# Connector.net
KiCad netlist of a schematic drawn in Altium Designer
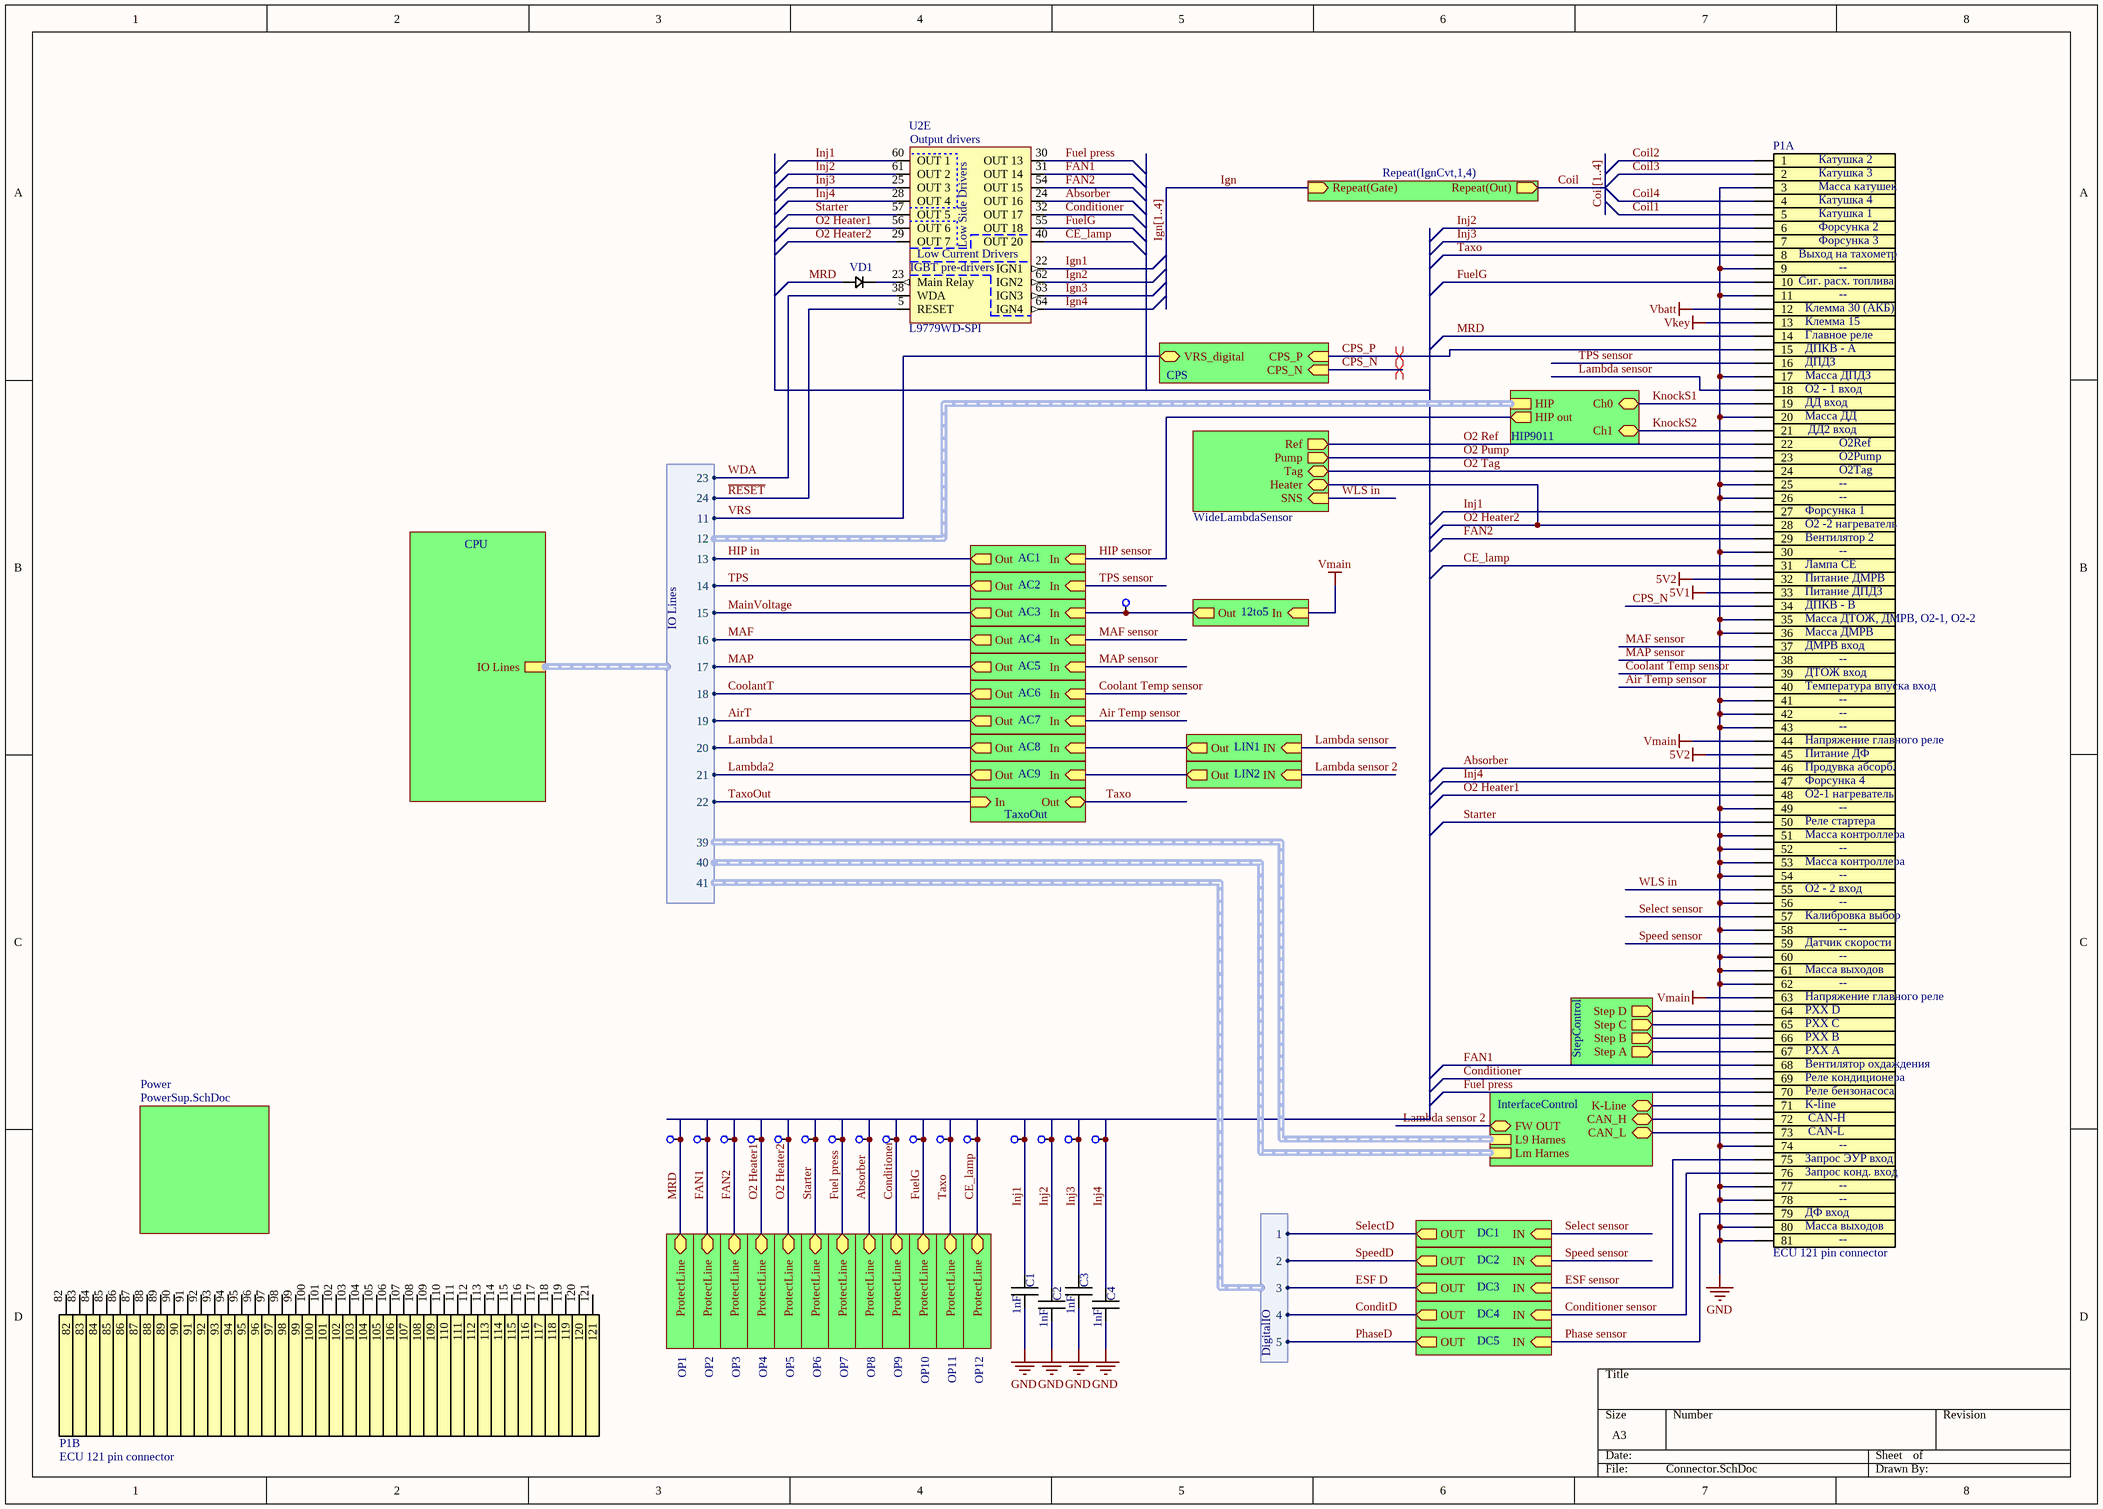
[diagram p0: Connector.SchDoc]

(export (version "E")
  (design (tool "Eeschema 10.0.6"))
  (components
    (comp (ref "C1")
      (value "1nF")
      (footprint "SMD 0603")
      (description "CC0603KRX7R9BB102")
      (libsource (lib "Maks_lib") (part "Capasitor"))
    )
    (comp (ref "C2")
      (value "1nF")
      (footprint "SMD 0603")
      (description "CC0603KRX7R9BB102")
      (libsource (lib "Maks_lib") (part "Capasitor"))
    )
    (comp (ref "C3")
      (value "1nF")
      (footprint "SMD 0603")
      (description "CC0603KRX7R9BB102")
      (libsource (lib "Maks_lib") (part "Capasitor"))
    )
    (comp (ref "C4")
      (value "1nF")
      (footprint "SMD 0603")
      (description "CC0603KRX7R9BB102")
      (libsource (lib "Maks_lib") (part "Capasitor"))
    )
    (comp (ref "P1")
      (value "ECU 121 pin connector")
      (footprint "1241434-1")
      (libsource (lib "Maks_lib") (part "1241434-1"))
    )
    (comp (ref "TP1")
      (value "TestPoint")
      (footprint "TESTPOINT")
      (description "testPoint")
      (libsource (lib "Maks_lib") (part "TestPoint"))
    )
    (comp (ref "TP2")
      (value "TestPoint")
      (footprint "TESTPOINT")
      (description "testPoint")
      (libsource (lib "Maks_lib") (part "TestPoint"))
    )
    (comp (ref "TP3")
      (value "TestPoint")
      (footprint "TESTPOINT")
      (description "testPoint")
      (libsource (lib "Maks_lib") (part "TestPoint"))
    )
    (comp (ref "TP4")
      (value "TestPoint")
      (footprint "TESTPOINT")
      (description "testPoint")
      (libsource (lib "Maks_lib") (part "TestPoint"))
    )
    (comp (ref "TP5")
      (value "TestPoint")
      (footprint "TESTPOINT")
      (description "testPoint")
      (libsource (lib "Maks_lib") (part "TestPoint"))
    )
    (comp (ref "TP6")
      (value "TestPoint")
      (footprint "TESTPOINT")
      (description "testPoint")
      (libsource (lib "Maks_lib") (part "TestPoint"))
    )
    (comp (ref "TP7")
      (value "TestPoint")
      (footprint "TESTPOINT")
      (description "testPoint")
      (libsource (lib "Maks_lib") (part "TestPoint"))
    )
    (comp (ref "TP8")
      (value "TestPoint")
      (footprint "TESTPOINT")
      (description "testPoint")
      (libsource (lib "Maks_lib") (part "TestPoint"))
    )
    (comp (ref "TP9")
      (value "TestPoint")
      (footprint "TESTPOINT")
      (description "testPoint")
      (libsource (lib "Maks_lib") (part "TestPoint"))
    )
    (comp (ref "TP10")
      (value "TestPoint")
      (footprint "TESTPOINT")
      (description "testPoint")
      (libsource (lib "Maks_lib") (part "TestPoint"))
    )
    (comp (ref "TP11")
      (value "TestPoint")
      (footprint "TESTPOINT")
      (description "testPoint")
      (libsource (lib "Maks_lib") (part "TestPoint"))
    )
    (comp (ref "TP12")
      (value "TestPoint")
      (footprint "TESTPOINT")
      (description "testPoint")
      (libsource (lib "Maks_lib") (part "TestPoint"))
    )
    (comp (ref "TP13")
      (value "TestPoint")
      (footprint "TESTPOINT")
      (description "testPoint")
      (libsource (lib "Maks_lib") (part "TestPoint"))
    )
    (comp (ref "TP14")
      (value "TestPoint")
      (footprint "TESTPOINT")
      (description "testPoint")
      (libsource (lib "Maks_lib") (part "TestPoint"))
    )
    (comp (ref "TP15")
      (value "TestPoint")
      (footprint "TESTPOINT")
      (description "testPoint")
      (libsource (lib "Maks_lib") (part "TestPoint"))
    )
    (comp (ref "TP16")
      (value "TestPoint")
      (footprint "TESTPOINT")
      (description "testPoint")
      (libsource (lib "Maks_lib") (part "TestPoint"))
    )
    (comp (ref "TP17")
      (value "TestPoint")
      (footprint "TESTPOINT")
      (description "testPoint")
      (libsource (lib "Maks_lib") (part "TestPoint"))
    )
    (comp (ref "U2")
      (value "L9779WD-SPI")
      (footprint "HiQUAD-64")
      (description "Multifunction IC for engine management system")
      (libsource (lib "Maks_lib") (part "L9779WD-SPI"))
    )
    (comp (ref "VD1")
      (value "Diode")
      (footprint "DO-214AC")
      (description "STTH2R02A")
      (libsource (lib "Maks_lib") (part "Diode"))
    )
  )
  (nets
    (net (code "3") (name "/Absorber") (class "Default")
      (node (ref "P1") (pin "46") (pinfunction "46_46") (pintype "passive"))
      (node (ref "TP8") (pin "0") (pinfunction "0_0") (pintype "passive"))
      (node (ref "U2") (pin "24") (pinfunction "OUT_16_24") (pintype "passive"))
    )
    (net (code "4") (name "/Air Temp sensor") (class "Default")
      (node (ref "P1") (pin "40") (pinfunction "40_40") (pintype "passive"))
    )
    (net (code "6") (name "/CAN_H") (class "Default")
      (node (ref "P1") (pin "72") (pinfunction "72_72") (pintype "passive"))
    )
    (net (code "7") (name "/CAN_L") (class "Default")
      (node (ref "P1") (pin "73") (pinfunction "73_73") (pintype "passive"))
    )
    (net (code "8") (name "/CE_lamp") (class "Default")
      (node (ref "P1") (pin "31") (pinfunction "31_31") (pintype "passive"))
      (node (ref "TP12") (pin "0") (pinfunction "0_0") (pintype "passive"))
      (node (ref "U2") (pin "40") (pinfunction "OUT_20_40") (pintype "passive"))
    )
    (net (code "9") (name "/CPS_N") (class "Default")
      (node (ref "P1") (pin "34") (pinfunction "34_34") (pintype "passive"))
    )
    (net (code "10") (name "/CPS_P") (class "Default")
      (node (ref "P1") (pin "15") (pinfunction "15_15") (pintype "passive"))
    )
    (net (code "12") (name "/Coil1") (class "Default")
      (node (ref "P1") (pin "5") (pinfunction "5_5") (pintype "passive"))
    )
    (net (code "13") (name "/Coil2") (class "Default")
      (node (ref "P1") (pin "1") (pinfunction "1_1") (pintype "passive"))
    )
    (net (code "14") (name "/Coil3") (class "Default")
      (node (ref "P1") (pin "2") (pinfunction "2_2") (pintype "passive"))
    )
    (net (code "15") (name "/Coil4") (class "Default")
      (node (ref "P1") (pin "4") (pinfunction "4_4") (pintype "passive"))
    )
    (net (code "18") (name "/Conditioner") (class "Default")
      (node (ref "P1") (pin "69") (pinfunction "69_69") (pintype "passive"))
      (node (ref "TP9") (pin "0") (pinfunction "0_0") (pintype "passive"))
      (node (ref "U2") (pin "32") (pinfunction "OUT_17_32") (pintype "passive"))
    )
    (net (code "19") (name "/Conditioner sensor") (class "Default")
      (node (ref "P1") (pin "76") (pinfunction "76_76") (pintype "passive"))
    )
    (net (code "20") (name "/Coolant Temp sensor") (class "Default")
      (node (ref "P1") (pin "39") (pinfunction "39_39") (pintype "passive"))
    )
    (net (code "23") (name "/ESF sensor") (class "Default")
      (node (ref "P1") (pin "75") (pinfunction "75_75") (pintype "passive"))
    )
    (net (code "24") (name "/FAN1") (class "Default")
      (node (ref "P1") (pin "68") (pinfunction "68_68") (pintype "passive"))
      (node (ref "TP2") (pin "0") (pinfunction "0_0") (pintype "passive"))
      (node (ref "U2") (pin "31") (pinfunction "OUT_14_31") (pintype "passive"))
    )
    (net (code "25") (name "/FAN2") (class "Default")
      (node (ref "P1") (pin "29") (pinfunction "29_29") (pintype "passive"))
      (node (ref "TP3") (pin "0") (pinfunction "0_0") (pintype "passive"))
      (node (ref "U2") (pin "54") (pinfunction "OUT_15_54") (pintype "passive"))
    )
    (net (code "26") (name "/Fuel press") (class "Default")
      (node (ref "P1") (pin "70") (pinfunction "70_70") (pintype "passive"))
      (node (ref "TP7") (pin "0") (pinfunction "0_0") (pintype "passive"))
      (node (ref "U2") (pin "30") (pinfunction "OUT_13_30") (pintype "passive"))
    )
    (net (code "27") (name "/FuelG") (class "Default")
      (node (ref "P1") (pin "10") (pinfunction "10_10") (pintype "passive"))
      (node (ref "TP10") (pin "0") (pinfunction "0_0") (pintype "passive"))
      (node (ref "U2") (pin "55") (pinfunction "OUT_18_55") (pintype "passive"))
    )
    (net (code "33") (name "/Ign1") (class "Default")
      (node (ref "U2") (pin "22") (pinfunction "IGN1_22") (pintype "output"))
    )
    (net (code "34") (name "/Ign2") (class "Default")
      (node (ref "U2") (pin "62") (pinfunction "IGN2_62") (pintype "output"))
    )
    (net (code "35") (name "/Ign3") (class "Default")
      (node (ref "U2") (pin "63") (pinfunction "IGN3_63") (pintype "output"))
    )
    (net (code "36") (name "/Ign4") (class "Default")
      (node (ref "U2") (pin "64") (pinfunction "IGN4_64") (pintype "output"))
    )
    (net (code "38") (name "/Inj1") (class "Default")
      (node (ref "C1") (pin "2") (pinfunction "2_2") (pintype "passive"))
      (node (ref "P1") (pin "27") (pinfunction "27_27") (pintype "passive"))
      (node (ref "TP13") (pin "0") (pinfunction "0_0") (pintype "passive"))
      (node (ref "U2") (pin "60") (pinfunction "OUT_1_60") (pintype "passive"))
    )
    (net (code "39") (name "/Inj2") (class "Default")
      (node (ref "C2") (pin "2") (pinfunction "2_2") (pintype "passive"))
      (node (ref "P1") (pin "6") (pinfunction "6_6") (pintype "passive"))
      (node (ref "TP14") (pin "0") (pinfunction "0_0") (pintype "passive"))
      (node (ref "U2") (pin "61") (pinfunction "OUT_2_61") (pintype "passive"))
    )
    (net (code "40") (name "/Inj3") (class "Default")
      (node (ref "C3") (pin "2") (pinfunction "2_2") (pintype "passive"))
      (node (ref "P1") (pin "7") (pinfunction "7_7") (pintype "passive"))
      (node (ref "TP15") (pin "0") (pinfunction "0_0") (pintype "passive"))
      (node (ref "U2") (pin "25") (pinfunction "OUT_3_25") (pintype "passive"))
    )
    (net (code "41") (name "/Inj4") (class "Default")
      (node (ref "C4") (pin "2") (pinfunction "2_2") (pintype "passive"))
      (node (ref "P1") (pin "47") (pinfunction "47_47") (pintype "passive"))
      (node (ref "TP16") (pin "0") (pinfunction "0_0") (pintype "passive"))
      (node (ref "U2") (pin "28") (pinfunction "OUT_4_28") (pintype "passive"))
    )
    (net (code "42") (name "/K-Line") (class "Default")
      (node (ref "P1") (pin "71") (pinfunction "71_71") (pintype "passive"))
    )
    (net (code "43") (name "/KnockS1") (class "Default")
      (node (ref "P1") (pin "19") (pinfunction "19_19") (pintype "passive"))
    )
    (net (code "44") (name "/KnockS2") (class "Default")
      (node (ref "P1") (pin "21") (pinfunction "21_21") (pintype "passive"))
    )
    (net (code "46") (name "/Lambda sensor") (class "Default")
      (node (ref "P1") (pin "18") (pinfunction "18_18") (pintype "passive"))
    )
    (net (code "52") (name "/MAF sensor") (class "Default")
      (node (ref "P1") (pin "37") (pinfunction "37_37") (pintype "passive"))
    )
    (net (code "54") (name "/MAP sensor") (class "Default")
      (node (ref "P1") (pin "38") (pinfunction "38_38") (pintype "passive"))
    )
    (net (code "55") (name "/MRD") (class "Default")
      (node (ref "P1") (pin "14") (pinfunction "14_14") (pintype "passive"))
      (node (ref "TP1") (pin "0") (pinfunction "0_0") (pintype "passive"))
      (node (ref "VD1") (pin "0") (pinfunction "0_0") (pintype "passive"))
    )
    (net (code "57") (name "/O2 Heater1") (class "Default")
      (node (ref "P1") (pin "48") (pinfunction "48_48") (pintype "passive"))
      (node (ref "TP4") (pin "0") (pinfunction "0_0") (pintype "passive"))
      (node (ref "U2") (pin "56") (pinfunction "OUT_6_56") (pintype "passive"))
    )
    (net (code "58") (name "/O2 Heater2") (class "Default")
      (node (ref "P1") (pin "28") (pinfunction "28_28") (pintype "passive"))
      (node (ref "TP5") (pin "0") (pinfunction "0_0") (pintype "passive"))
      (node (ref "U2") (pin "29") (pinfunction "OUT_7_29") (pintype "passive"))
    )
    (net (code "59") (name "/O2 Pump") (class "Default")
      (node (ref "P1") (pin "23") (pinfunction "23_23") (pintype "passive"))
    )
    (net (code "60") (name "/O2 Ref") (class "Default")
      (node (ref "P1") (pin "22") (pinfunction "22_22") (pintype "passive"))
    )
    (net (code "61") (name "/O2 Tag") (class "Default")
      (node (ref "P1") (pin "24") (pinfunction "24_24") (pintype "passive"))
    )
    (net (code "62") (name "/Out") (class "Default")
      (node (ref "TP17") (pin "0") (pinfunction "0_0") (pintype "passive"))
    )
    (net (code "65") (name "/Phase sensor") (class "Default")
      (node (ref "P1") (pin "79") (pinfunction "79_79") (pintype "passive"))
    )
    (net (code "67") (name "/RESET") (class "Default")
      (node (ref "U2") (pin "5") (pinfunction "RESET_5") (pintype "passive"))
    )
    (net (code "68") (name "/Select sensor") (class "Default")
      (node (ref "P1") (pin "57") (pinfunction "57_57") (pintype "passive"))
    )
    (net (code "70") (name "/Speed sensor") (class "Default")
      (node (ref "P1") (pin "59") (pinfunction "59_59") (pintype "passive"))
    )
    (net (code "72") (name "/Starter") (class "Default")
      (node (ref "P1") (pin "50") (pinfunction "50_50") (pintype "passive"))
      (node (ref "TP6") (pin "0") (pinfunction "0_0") (pintype "passive"))
      (node (ref "U2") (pin "57") (pinfunction "OUT_5_57") (pintype "passive"))
    )
    (net (code "73") (name "/Step A") (class "Default")
      (node (ref "P1") (pin "67") (pinfunction "67_67") (pintype "passive"))
    )
    (net (code "74") (name "/Step B") (class "Default")
      (node (ref "P1") (pin "66") (pinfunction "66_66") (pintype "passive"))
    )
    (net (code "75") (name "/Step C") (class "Default")
      (node (ref "P1") (pin "65") (pinfunction "65_65") (pintype "passive"))
    )
    (net (code "76") (name "/Step D") (class "Default")
      (node (ref "P1") (pin "64") (pinfunction "64_64") (pintype "passive"))
    )
    (net (code "78") (name "/TPS sensor") (class "Default")
      (node (ref "P1") (pin "16") (pinfunction "16_16") (pintype "passive"))
    )
    (net (code "79") (name "/Taxo") (class "Default")
      (node (ref "P1") (pin "8") (pinfunction "8_8") (pintype "passive"))
      (node (ref "TP11") (pin "0") (pinfunction "0_0") (pintype "passive"))
    )
    (net (code "82") (name "/WDA") (class "Default")
      (node (ref "U2") (pin "38") (pinfunction "WDA_38") (pintype "passive"))
    )
    (net (code "83") (name "/WLS in") (class "Default")
      (node (ref "P1") (pin "55") (pinfunction "55_55") (pintype "passive"))
    )
    (net (code "85") (name "5V1") (class "Default")
      (node (ref "P1") (pin "33") (pinfunction "33_33") (pintype "passive"))
    )
    (net (code "86") (name "5V2") (class "Default")
      (node (ref "P1") (pin "32") (pinfunction "32_32") (pintype "passive"))
      (node (ref "P1") (pin "45") (pinfunction "45_45") (pintype "passive"))
    )
    (net (code "87") (name "GND") (class "Default")
      (node (ref "C1") (pin "1") (pinfunction "1_1") (pintype "passive"))
      (node (ref "C2") (pin "1") (pinfunction "1_1") (pintype "passive"))
      (node (ref "C3") (pin "1") (pinfunction "1_1") (pintype "passive"))
      (node (ref "C4") (pin "1") (pinfunction "1_1") (pintype "passive"))
      (node (ref "P1") (pin "11") (pinfunction "11_11") (pintype "passive"))
      (node (ref "P1") (pin "17") (pinfunction "17_17") (pintype "passive"))
      (node (ref "P1") (pin "20") (pinfunction "20_20") (pintype "passive"))
      (node (ref "P1") (pin "25") (pinfunction "25_25") (pintype "passive"))
      (node (ref "P1") (pin "26") (pinfunction "26_26") (pintype "passive"))
      (node (ref "P1") (pin "3") (pinfunction "3_3") (pintype "passive"))
      (node (ref "P1") (pin "30") (pinfunction "30_30") (pintype "passive"))
      (node (ref "P1") (pin "35") (pinfunction "35_35") (pintype "passive"))
      (node (ref "P1") (pin "36") (pinfunction "36_36") (pintype "passive"))
      (node (ref "P1") (pin "41") (pinfunction "41_41") (pintype "passive"))
      (node (ref "P1") (pin "42") (pinfunction "42_42") (pintype "passive"))
      (node (ref "P1") (pin "43") (pinfunction "43_43") (pintype "passive"))
      (node (ref "P1") (pin "49") (pinfunction "49_49") (pintype "passive"))
      (node (ref "P1") (pin "51") (pinfunction "51_51") (pintype "passive"))
      (node (ref "P1") (pin "52") (pinfunction "52_52") (pintype "passive"))
      (node (ref "P1") (pin "53") (pinfunction "53_53") (pintype "passive"))
      (node (ref "P1") (pin "54") (pinfunction "54_54") (pintype "passive"))
      (node (ref "P1") (pin "56") (pinfunction "56_56") (pintype "passive"))
      (node (ref "P1") (pin "58") (pinfunction "58_58") (pintype "passive"))
      (node (ref "P1") (pin "60") (pinfunction "60_60") (pintype "passive"))
      (node (ref "P1") (pin "61") (pinfunction "61_61") (pintype "passive"))
      (node (ref "P1") (pin "62") (pinfunction "62_62") (pintype "passive"))
      (node (ref "P1") (pin "74") (pinfunction "74_74") (pintype "passive"))
      (node (ref "P1") (pin "77") (pinfunction "77_77") (pintype "passive"))
      (node (ref "P1") (pin "78") (pinfunction "78_78") (pintype "passive"))
      (node (ref "P1") (pin "80") (pinfunction "80_80") (pintype "passive"))
      (node (ref "P1") (pin "81") (pinfunction "81_81") (pintype "passive"))
      (node (ref "P1") (pin "9") (pinfunction "9_9") (pintype "passive"))
    )
    (net (code "88") (name "Net-(U2E-Main_Relay)") (class "Default")
      (node (ref "U2") (pin "23") (pinfunction "Main_Relay_23") (pintype "output"))
      (node (ref "VD1") (pin "1") (pinfunction "1_1") (pintype "passive"))
    )
    (net (code "89") (name "Vbatt") (class "Default")
      (node (ref "P1") (pin "12") (pinfunction "12_12") (pintype "passive"))
    )
    (net (code "90") (name "Vkey") (class "Default")
      (node (ref "P1") (pin "13") (pinfunction "13_13") (pintype "passive"))
    )
    (net (code "91") (name "Vmain") (class "Default")
      (node (ref "P1") (pin "44") (pinfunction "44_44") (pintype "passive"))
      (node (ref "P1") (pin "63") (pinfunction "63_63") (pintype "passive"))
    )
    (net (code "92") (name "unconnected-(P1-Pad82)") (class "Default")
      (node (ref "P1") (pin "82") (pinfunction "82_82") (pintype "passive"))
    )
    (net (code "93") (name "unconnected-(P1-Pad83)") (class "Default")
      (node (ref "P1") (pin "83") (pinfunction "83_83") (pintype "passive"))
    )
    (net (code "94") (name "unconnected-(P1-Pad84)") (class "Default")
      (node (ref "P1") (pin "84") (pinfunction "84_84") (pintype "passive"))
    )
    (net (code "95") (name "unconnected-(P1-Pad85)") (class "Default")
      (node (ref "P1") (pin "85") (pinfunction "85_85") (pintype "passive"))
    )
    (net (code "96") (name "unconnected-(P1-Pad86)") (class "Default")
      (node (ref "P1") (pin "86") (pinfunction "86_86") (pintype "passive"))
    )
    (net (code "97") (name "unconnected-(P1-Pad87)") (class "Default")
      (node (ref "P1") (pin "87") (pinfunction "87_87") (pintype "passive"))
    )
    (net (code "98") (name "unconnected-(P1-Pad88)") (class "Default")
      (node (ref "P1") (pin "88") (pinfunction "88_88") (pintype "passive"))
    )
    (net (code "99") (name "unconnected-(P1-Pad89)") (class "Default")
      (node (ref "P1") (pin "89") (pinfunction "89_89") (pintype "passive"))
    )
    (net (code "100") (name "unconnected-(P1-Pad90)") (class "Default")
      (node (ref "P1") (pin "90") (pinfunction "90_90") (pintype "passive"))
    )
    (net (code "101") (name "unconnected-(P1-Pad91)") (class "Default")
      (node (ref "P1") (pin "91") (pinfunction "91_91") (pintype "passive"))
    )
    (net (code "102") (name "unconnected-(P1-Pad92)") (class "Default")
      (node (ref "P1") (pin "92") (pinfunction "92_92") (pintype "passive"))
    )
    (net (code "103") (name "unconnected-(P1-Pad93)") (class "Default")
      (node (ref "P1") (pin "93") (pinfunction "93_93") (pintype "passive"))
    )
    (net (code "104") (name "unconnected-(P1-Pad94)") (class "Default")
      (node (ref "P1") (pin "94") (pinfunction "94_94") (pintype "passive"))
    )
    (net (code "105") (name "unconnected-(P1-Pad95)") (class "Default")
      (node (ref "P1") (pin "95") (pinfunction "95_95") (pintype "passive"))
    )
    (net (code "106") (name "unconnected-(P1-Pad96)") (class "Default")
      (node (ref "P1") (pin "96") (pinfunction "96_96") (pintype "passive"))
    )
    (net (code "107") (name "unconnected-(P1-Pad97)") (class "Default")
      (node (ref "P1") (pin "97") (pinfunction "97_97") (pintype "passive"))
    )
    (net (code "108") (name "unconnected-(P1-Pad98)") (class "Default")
      (node (ref "P1") (pin "98") (pinfunction "98_98") (pintype "passive"))
    )
    (net (code "109") (name "unconnected-(P1-Pad99)") (class "Default")
      (node (ref "P1") (pin "99") (pinfunction "99_99") (pintype "passive"))
    )
    (net (code "110") (name "unconnected-(P1-Pad100)") (class "Default")
      (node (ref "P1") (pin "100") (pinfunction "100_100") (pintype "passive"))
    )
    (net (code "111") (name "unconnected-(P1-Pad101)") (class "Default")
      (node (ref "P1") (pin "101") (pinfunction "101_101") (pintype "passive"))
    )
    (net (code "112") (name "unconnected-(P1-Pad102)") (class "Default")
      (node (ref "P1") (pin "102") (pinfunction "102_102") (pintype "passive"))
    )
    (net (code "113") (name "unconnected-(P1-Pad103)") (class "Default")
      (node (ref "P1") (pin "103") (pinfunction "103_103") (pintype "passive"))
    )
    (net (code "114") (name "unconnected-(P1-Pad104)") (class "Default")
      (node (ref "P1") (pin "104") (pinfunction "104_104") (pintype "passive"))
    )
    (net (code "115") (name "unconnected-(P1-Pad105)") (class "Default")
      (node (ref "P1") (pin "105") (pinfunction "105_105") (pintype "passive"))
    )
    (net (code "116") (name "unconnected-(P1-Pad106)") (class "Default")
      (node (ref "P1") (pin "106") (pinfunction "106_106") (pintype "passive"))
    )
    (net (code "117") (name "unconnected-(P1-Pad107)") (class "Default")
      (node (ref "P1") (pin "107") (pinfunction "107_107") (pintype "passive"))
    )
    (net (code "118") (name "unconnected-(P1-Pad108)") (class "Default")
      (node (ref "P1") (pin "108") (pinfunction "108_108") (pintype "passive"))
    )
    (net (code "119") (name "unconnected-(P1-Pad109)") (class "Default")
      (node (ref "P1") (pin "109") (pinfunction "109_109") (pintype "passive"))
    )
    (net (code "120") (name "unconnected-(P1-Pad110)") (class "Default")
      (node (ref "P1") (pin "110") (pinfunction "110_110") (pintype "passive"))
    )
    (net (code "121") (name "unconnected-(P1-Pad111)") (class "Default")
      (node (ref "P1") (pin "111") (pinfunction "111_111") (pintype "passive"))
    )
    (net (code "122") (name "unconnected-(P1-Pad112)") (class "Default")
      (node (ref "P1") (pin "112") (pinfunction "112_112") (pintype "passive"))
    )
    (net (code "123") (name "unconnected-(P1-Pad113)") (class "Default")
      (node (ref "P1") (pin "113") (pinfunction "113_113") (pintype "passive"))
    )
    (net (code "124") (name "unconnected-(P1-Pad114)") (class "Default")
      (node (ref "P1") (pin "114") (pinfunction "114_114") (pintype "passive"))
    )
    (net (code "125") (name "unconnected-(P1-Pad115)") (class "Default")
      (node (ref "P1") (pin "115") (pinfunction "115_115") (pintype "passive"))
    )
    (net (code "126") (name "unconnected-(P1-Pad116)") (class "Default")
      (node (ref "P1") (pin "116") (pinfunction "116_116") (pintype "passive"))
    )
    (net (code "127") (name "unconnected-(P1-Pad117)") (class "Default")
      (node (ref "P1") (pin "117") (pinfunction "117_117") (pintype "passive"))
    )
    (net (code "128") (name "unconnected-(P1-Pad118)") (class "Default")
      (node (ref "P1") (pin "118") (pinfunction "118_118") (pintype "passive"))
    )
    (net (code "129") (name "unconnected-(P1-Pad119)") (class "Default")
      (node (ref "P1") (pin "119") (pinfunction "119_119") (pintype "passive"))
    )
    (net (code "130") (name "unconnected-(P1-Pad120)") (class "Default")
      (node (ref "P1") (pin "120") (pinfunction "120_120") (pintype "passive"))
    )
    (net (code "131") (name "unconnected-(P1-Pad121)") (class "Default")
      (node (ref "P1") (pin "121") (pinfunction "121_121") (pintype "passive"))
    )
  )
)
